# Sheet1.net
KiCad netlist of a schematic drawn in Altium Designer
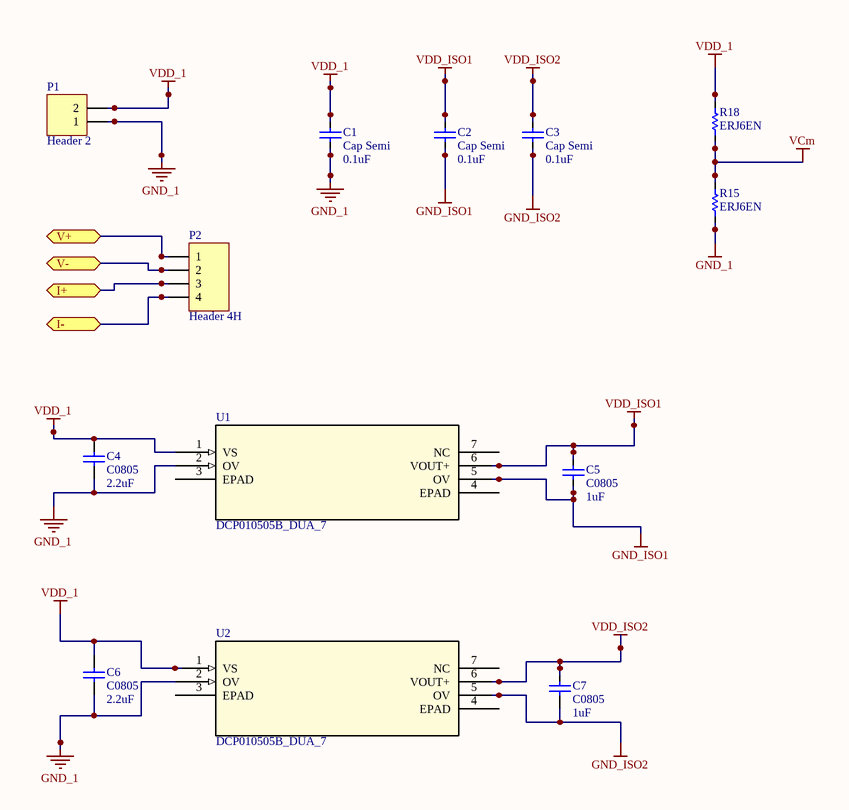
[diagram p0: Sheet1.SchDoc]

(export (version "E")
  (design (tool "Eeschema 10.0.6"))
  (components
    (comp (ref "C1")
      (value "Cap Semi")
      (footprint "C1206")
      (description "Capacitor (Semiconductor SIM Model)")
      (fields (field (name "ALTIUM_VALUE") "0.1uF") (field (name "PUBLISHER") "Altium Limited"))
      (libsource (lib "Miscellaneous Devices") (part "Cap Semi"))
    )
    (comp (ref "C2")
      (value "Cap Semi")
      (footprint "C1206")
      (description "Capacitor (Semiconductor SIM Model)")
      (fields (field (name "ALTIUM_VALUE") "0.1uF") (field (name "PUBLISHER") "Altium Limited"))
      (libsource (lib "Miscellaneous Devices") (part "Cap Semi"))
    )
    (comp (ref "C3")
      (value "Cap Semi")
      (footprint "C1206")
      (description "Capacitor (Semiconductor SIM Model)")
      (fields (field (name "ALTIUM_VALUE") "0.1uF") (field (name "PUBLISHER") "Altium Limited"))
      (libsource (lib "Miscellaneous Devices") (part "Cap Semi"))
    )
    (comp (ref "C4")
      (value "C0805")
      (footprint "0805")
      (description "Ceramic Chip Capacitor - Standard")
      (fields (field (name "ALTIUM_VALUE") "2.2uF") (field (name "PUBLISHER") "Altium Limited"))
      (libsource (lib "KEMET Chip Capacitor") (part "C0805"))
    )
    (comp (ref "C5")
      (value "C0805")
      (footprint "0805")
      (description "Ceramic Chip Capacitor - Standard")
      (fields (field (name "ALTIUM_VALUE") "1uF") (field (name "PUBLISHER") "Altium Limited"))
      (libsource (lib "KEMET Chip Capacitor") (part "C0805"))
    )
    (comp (ref "C6")
      (value "C0805")
      (footprint "0805")
      (description "Ceramic Chip Capacitor - Standard")
      (fields (field (name "ALTIUM_VALUE") "2.2uF") (field (name "PUBLISHER") "Altium Limited"))
      (libsource (lib "KEMET Chip Capacitor") (part "C0805"))
    )
    (comp (ref "C7")
      (value "C0805")
      (footprint "0805")
      (description "Ceramic Chip Capacitor - Standard")
      (fields (field (name "ALTIUM_VALUE") "1uF") (field (name "PUBLISHER") "Altium Limited"))
      (libsource (lib "KEMET Chip Capacitor") (part "C0805"))
    )
    (comp (ref "P1")
      (value "Header 2")
      (footprint "HDR1X2")
      (description "Header, 2-Pin")
      (fields (field (name "PUBLISHER") "Altium Limited"))
      (libsource (lib "Miscellaneous Connectors") (part "Header 2"))
    )
    (comp (ref "P2")
      (value "Header 4H")
      (footprint "HDR1X4H")
      (description "Header, 4-Pin, Right Angle")
      (fields (field (name "PUBLISHER") "Altium Limited"))
      (libsource (lib "Miscellaneous Connectors") (part "Header 4H"))
    )
    (comp (ref "R15")
      (value "ERJ6EN")
      (footprint "6-0805")
      (description "Precision Thick Film Chip Resistor, 10 Ohm to 2.2M Ohm Range, 1% Tolerance, 0805 Size, 0.1 W")
      (fields (field (name "PUBLISHER") "Altium Limited"))
      (libsource (lib "Panasonic Resistor") (part "ERJ6EN"))
    )
    (comp (ref "R18")
      (value "ERJ6EN")
      (footprint "6-0805")
      (description "Precision Thick Film Chip Resistor, 10 Ohm to 2.2M Ohm Range, 1% Tolerance, 0805 Size, 0.1 W")
      (fields (field (name "PUBLISHER") "Altium Limited"))
      (libsource (lib "Panasonic Resistor") (part "ERJ6EN"))
    )
    (comp (ref "U1")
      (value "DCP010505B_DUA_7")
      (footprint "DUA7")
      (description "Imported")
      (fields
        (field (name "MANUFACTURER") "Texas Instruments")
        (field (name "GENERIC_PART_NUMBER") "DCP010505B")
      )
      (libsource (lib "2018-03-09_10-57-31") (part "DCP010505B_DUA_7"))
    )
    (comp (ref "U2")
      (value "DCP010505B_DUA_7")
      (footprint "DUA7")
      (description "Imported")
      (fields
        (field (name "MANUFACTURER") "Texas Instruments")
        (field (name "GENERIC_PART_NUMBER") "DCP010505B")
      )
      (libsource (lib "2018-03-09_10-57-31") (part "DCP010505B_DUA_7"))
    )
  )
  (nets
    (net (code "1") (name "/I+") (class "Default")
      (node (ref "P2") (pin "3") (pinfunction "3_3") (pintype "passive"))
    )
    (net (code "2") (name "/I-") (class "Default")
      (node (ref "P2") (pin "4") (pinfunction "4_4") (pintype "passive"))
    )
    (net (code "3") (name "/V+") (class "Default")
      (node (ref "P2") (pin "1") (pinfunction "1_1") (pintype "passive"))
    )
    (net (code "4") (name "/V-") (class "Default")
      (node (ref "P2") (pin "2") (pinfunction "2_2") (pintype "passive"))
    )
    (net (code "5") (name "GND_1") (class "Default")
      (node (ref "C1") (pin "1") (pinfunction "1_1") (pintype "passive"))
      (node (ref "C4") (pin "1") (pinfunction "1_1") (pintype "passive"))
      (node (ref "C6") (pin "1") (pinfunction "1_1") (pintype "passive"))
      (node (ref "P1") (pin "1") (pinfunction "1_1") (pintype "passive"))
      (node (ref "R15") (pin "1") (pinfunction "1_1") (pintype "passive"))
      (node (ref "U1") (pin "2") (pinfunction "OV_2") (pintype "input"))
      (node (ref "U2") (pin "2") (pinfunction "OV_2") (pintype "input"))
    )
    (net (code "6") (name "GND_ISO1") (class "Default")
      (node (ref "C2") (pin "1") (pinfunction "1_1") (pintype "passive"))
      (node (ref "C5") (pin "1") (pinfunction "1_1") (pintype "passive"))
      (node (ref "U1") (pin "5") (pinfunction "OV_5") (pintype "power_in"))
    )
    (net (code "7") (name "GND_ISO2") (class "Default")
      (node (ref "C3") (pin "1") (pinfunction "1_1") (pintype "passive"))
      (node (ref "C7") (pin "1") (pinfunction "1_1") (pintype "passive"))
      (node (ref "U2") (pin "5") (pinfunction "OV_5") (pintype "power_in"))
    )
    (net (code "8") (name "VCm") (class "Default")
      (node (ref "R15") (pin "2") (pinfunction "2_2") (pintype "passive"))
      (node (ref "R18") (pin "1") (pinfunction "1_1") (pintype "passive"))
    )
    (net (code "9") (name "VDD_1") (class "Default")
      (node (ref "C1") (pin "2") (pinfunction "2_2") (pintype "passive"))
      (node (ref "C4") (pin "2") (pinfunction "2_2") (pintype "passive"))
      (node (ref "C6") (pin "2") (pinfunction "2_2") (pintype "passive"))
      (node (ref "P1") (pin "2") (pinfunction "2_2") (pintype "passive"))
      (node (ref "R18") (pin "2") (pinfunction "2_2") (pintype "passive"))
      (node (ref "U1") (pin "1") (pinfunction "VS_1") (pintype "input"))
      (node (ref "U2") (pin "1") (pinfunction "VS_1") (pintype "input"))
    )
    (net (code "10") (name "VDD_ISO1") (class "Default")
      (node (ref "C2") (pin "2") (pinfunction "2_2") (pintype "passive"))
      (node (ref "C5") (pin "2") (pinfunction "2_2") (pintype "passive"))
      (node (ref "U1") (pin "6") (pinfunction "VOUT+_6") (pintype "power_in"))
    )
    (net (code "11") (name "VDD_ISO2") (class "Default")
      (node (ref "C3") (pin "2") (pinfunction "2_2") (pintype "passive"))
      (node (ref "C7") (pin "2") (pinfunction "2_2") (pintype "passive"))
      (node (ref "U2") (pin "6") (pinfunction "VOUT+_6") (pintype "power_in"))
    )
    (net (code "12") (name "unconnected-(U1-EPAD-Pad3)") (class "Default")
      (node (ref "U1") (pin "3") (pinfunction "EPAD_3") (pintype "power_in"))
    )
    (net (code "13") (name "unconnected-(U1-EPAD-Pad4)") (class "Default")
      (node (ref "U1") (pin "4") (pinfunction "EPAD_4") (pintype "power_in"))
    )
    (net (code "14") (name "unconnected-(U1-NC-Pad7)") (class "Default")
      (node (ref "U1") (pin "7") (pinfunction "NC_7") (pintype "passive"))
    )
    (net (code "15") (name "unconnected-(U2-EPAD-Pad3)") (class "Default")
      (node (ref "U2") (pin "3") (pinfunction "EPAD_3") (pintype "power_in"))
    )
    (net (code "16") (name "unconnected-(U2-EPAD-Pad4)") (class "Default")
      (node (ref "U2") (pin "4") (pinfunction "EPAD_4") (pintype "power_in"))
    )
    (net (code "17") (name "unconnected-(U2-NC-Pad7)") (class "Default")
      (node (ref "U2") (pin "7") (pinfunction "NC_7") (pintype "passive"))
    )
  )
)
